# DSP.net
KiCad netlist of a schematic drawn in Altium Designer
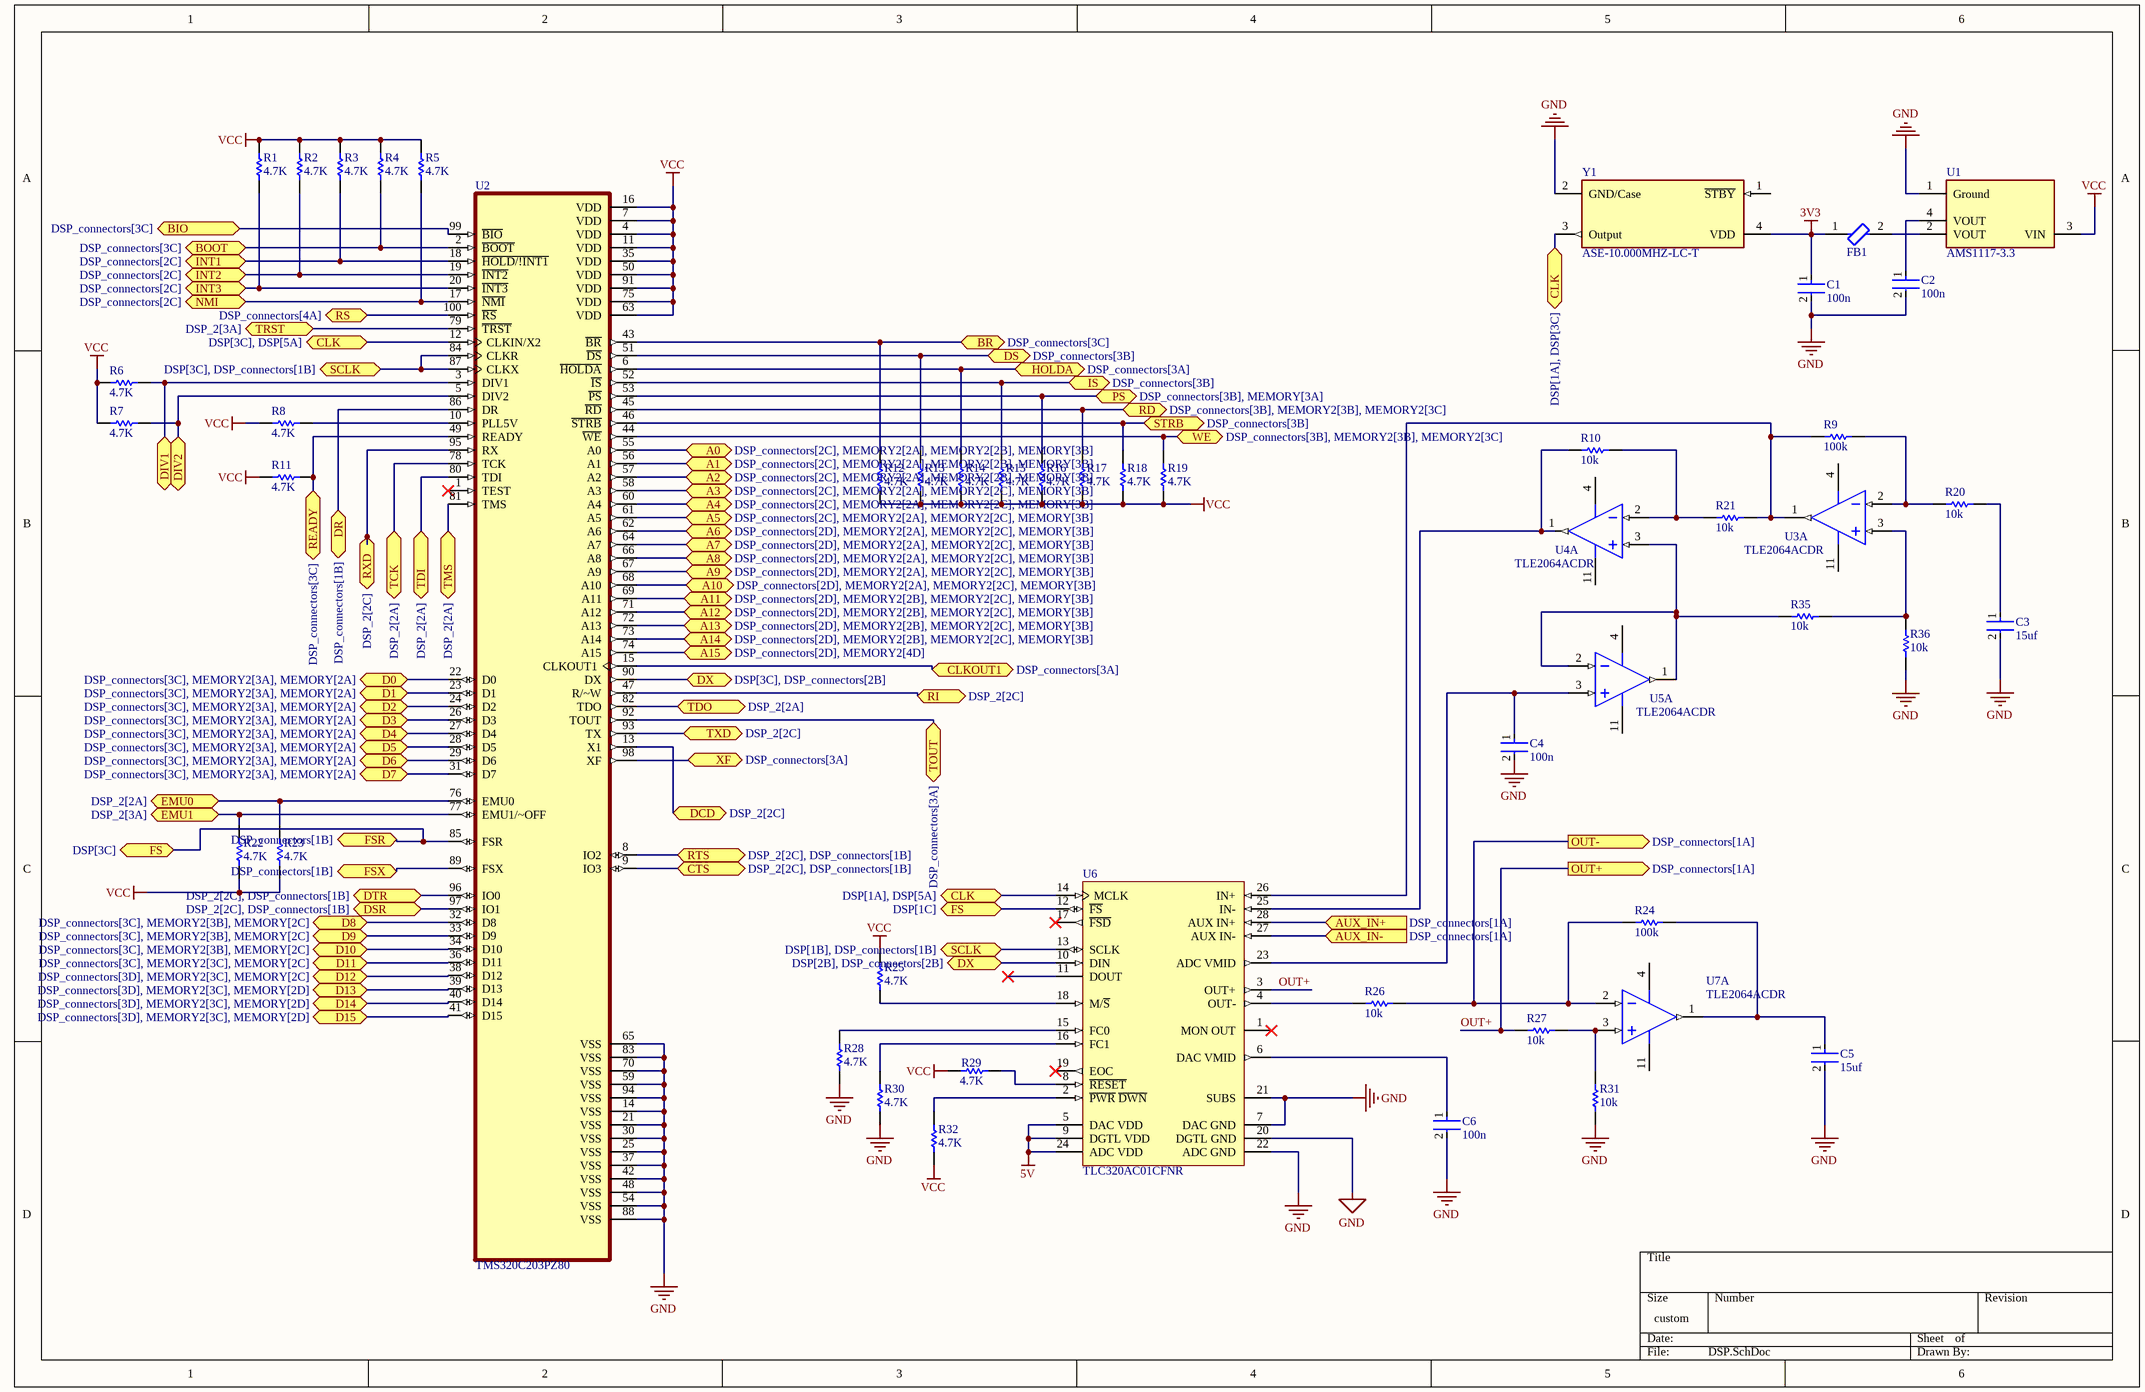
[diagram p0: DSP.SchDoc]

(export (version "E")
  (design (tool "Eeschema 10.0.6"))
  (components
    (comp (ref "C1")
      (value "100n")
      (footprint "FP-CL10-IPC_C")
      (description "Cap Ceramic 4.7uF 10V X5R ±10% Pad SMD 0603 +85°C T/R")
      (fields (field (name "TOLERANCE") "10%"))
      (libsource (lib "Altium Content Vault") (part "b4654b650e69147ec39a6b967a45e02"))
    )
    (comp (ref "C2")
      (value "100n")
      (footprint "FP-CL10-IPC_C")
      (description "Cap Ceramic 4.7uF 10V X5R ±10% Pad SMD 0603 +85°C T/R")
      (fields (field (name "TOLERANCE") "10%"))
      (libsource (lib "Altium Content Vault") (part "b4654b650e69147ec39a6b967a45e02"))
    )
    (comp (ref "C3")
      (value "15uf")
      (footprint "FP-CL10-IPC_C")
      (description "Cap Ceramic 4.7uF 10V X5R ±10% Pad SMD 0603 +85°C T/R")
      (fields (field (name "TOLERANCE") "10%"))
      (libsource (lib "Altium Content Vault") (part "b4654b650e69147ec39a6b967a45e02"))
    )
    (comp (ref "C4")
      (value "100n")
      (footprint "FP-CL10-IPC_C")
      (description "Cap Ceramic 4.7uF 10V X5R ±10% Pad SMD 0603 +85°C T/R")
      (fields (field (name "TOLERANCE") "10%"))
      (libsource (lib "Altium Content Vault") (part "b4654b650e69147ec39a6b967a45e02"))
    )
    (comp (ref "C5")
      (value "15uf")
      (footprint "FP-CL10-IPC_C")
      (description "Cap Ceramic 4.7uF 10V X5R ±10% Pad SMD 0603 +85°C T/R")
      (fields (field (name "TOLERANCE") "10%"))
      (libsource (lib "Altium Content Vault") (part "b4654b650e69147ec39a6b967a45e02"))
    )
    (comp (ref "C6")
      (value "100n")
      (footprint "FP-CL10-IPC_C")
      (description "Cap Ceramic 4.7uF 10V X5R ±10% Pad SMD 0603 +85°C T/R")
      (fields (field (name "TOLERANCE") "10%"))
      (libsource (lib "Altium Content Vault") (part "b4654b650e69147ec39a6b967a45e02"))
    )
    (comp (ref "FB1")
      (value "BLM18KG121TN1D")
      (footprint "FP-BLM18-0_15-t0_6-d1_2-IPC_A")
      (description "FERRITE BEAD 120 OHM 0603 1LN")
      (fields (field (name "TOLERANCE") "25%"))
      (libsource (lib "Altium Content Vault") (part "5f30dd21d616792df468990f7003faa"))
    )
    (comp (ref "R1")
      (value "4.7K")
      (footprint "RESC2013X60X35ML10T20")
      (fields (field (name "TOLERANCE") "5%") (field (name "MANUFACTURER") "Yageo"))
      (libsource (lib "Altium Content Vault") (part "RES-2"))
    )
    (comp (ref "R2")
      (value "4.7K")
      (footprint "RESC2013X60X35ML10T20")
      (fields (field (name "TOLERANCE") "5%") (field (name "MANUFACTURER") "Yageo"))
      (libsource (lib "Altium Content Vault") (part "RES-2"))
    )
    (comp (ref "R3")
      (value "4.7K")
      (footprint "RESC2013X60X35ML10T20")
      (fields (field (name "TOLERANCE") "5%") (field (name "MANUFACTURER") "Yageo"))
      (libsource (lib "Altium Content Vault") (part "RES-2"))
    )
    (comp (ref "R4")
      (value "4.7K")
      (footprint "RESC2013X60X35ML10T20")
      (fields (field (name "TOLERANCE") "5%") (field (name "MANUFACTURER") "Yageo"))
      (libsource (lib "Altium Content Vault") (part "RES-2"))
    )
    (comp (ref "R5")
      (value "4.7K")
      (footprint "RESC2013X60X35ML10T20")
      (fields (field (name "TOLERANCE") "5%") (field (name "MANUFACTURER") "Yageo"))
      (libsource (lib "Altium Content Vault") (part "RES-2"))
    )
    (comp (ref "R6")
      (value "4.7K")
      (footprint "RESC2013X60X35ML10T20")
      (fields (field (name "TOLERANCE") "5%") (field (name "MANUFACTURER") "Yageo"))
      (libsource (lib "Altium Content Vault") (part "RES-2"))
    )
    (comp (ref "R7")
      (value "4.7K")
      (footprint "RESC2013X60X35ML10T20")
      (fields (field (name "TOLERANCE") "5%") (field (name "MANUFACTURER") "Yageo"))
      (libsource (lib "Altium Content Vault") (part "RES-2"))
    )
    (comp (ref "R8")
      (value "4.7K")
      (footprint "RESC2013X60X35ML10T20")
      (fields (field (name "TOLERANCE") "5%") (field (name "MANUFACTURER") "Yageo"))
      (libsource (lib "Altium Content Vault") (part "RES-2"))
    )
    (comp (ref "R9")
      (value "100k")
      (footprint "RESC2013X60X35ML10T20")
      (fields (field (name "TOLERANCE") "5%") (field (name "MANUFACTURER") "Yageo"))
      (libsource (lib "Altium Content Vault") (part "RES-2"))
    )
    (comp (ref "R10")
      (value "10k")
      (footprint "RESC2013X60X35ML10T20")
      (fields (field (name "TOLERANCE") "5%") (field (name "MANUFACTURER") "Yageo"))
      (libsource (lib "Altium Content Vault") (part "RES-2"))
    )
    (comp (ref "R11")
      (value "4.7K")
      (footprint "RESC2013X60X35ML10T20")
      (fields (field (name "TOLERANCE") "5%") (field (name "MANUFACTURER") "Yageo"))
      (libsource (lib "Altium Content Vault") (part "RES-2"))
    )
    (comp (ref "R12")
      (value "4.7K")
      (footprint "RESC2013X60X35ML10T20")
      (fields (field (name "TOLERANCE") "5%") (field (name "MANUFACTURER") "Yageo"))
      (libsource (lib "Altium Content Vault") (part "RES-2"))
    )
    (comp (ref "R13")
      (value "4.7K")
      (footprint "RESC2013X60X35ML10T20")
      (fields (field (name "TOLERANCE") "5%") (field (name "MANUFACTURER") "Yageo"))
      (libsource (lib "Altium Content Vault") (part "RES-2"))
    )
    (comp (ref "R14")
      (value "4.7K")
      (footprint "RESC2013X60X35ML10T20")
      (fields (field (name "TOLERANCE") "5%") (field (name "MANUFACTURER") "Yageo"))
      (libsource (lib "Altium Content Vault") (part "RES-2"))
    )
    (comp (ref "R15")
      (value "4.7K")
      (footprint "RESC2013X60X35ML10T20")
      (fields (field (name "TOLERANCE") "5%") (field (name "MANUFACTURER") "Yageo"))
      (libsource (lib "Altium Content Vault") (part "RES-2"))
    )
    (comp (ref "R16")
      (value "4.7K")
      (footprint "RESC2013X60X35ML10T20")
      (fields (field (name "TOLERANCE") "5%") (field (name "MANUFACTURER") "Yageo"))
      (libsource (lib "Altium Content Vault") (part "RES-2"))
    )
    (comp (ref "R17")
      (value "4.7K")
      (footprint "RESC2013X60X35ML10T20")
      (fields (field (name "TOLERANCE") "5%") (field (name "MANUFACTURER") "Yageo"))
      (libsource (lib "Altium Content Vault") (part "RES-2"))
    )
    (comp (ref "R18")
      (value "4.7K")
      (footprint "RESC2013X60X35ML10T20")
      (fields (field (name "TOLERANCE") "5%") (field (name "MANUFACTURER") "Yageo"))
      (libsource (lib "Altium Content Vault") (part "RES-2"))
    )
    (comp (ref "R19")
      (value "4.7K")
      (footprint "RESC2013X60X35ML10T20")
      (fields (field (name "TOLERANCE") "5%") (field (name "MANUFACTURER") "Yageo"))
      (libsource (lib "Altium Content Vault") (part "RES-2"))
    )
    (comp (ref "R20")
      (value "10k")
      (footprint "RESC2013X60X35ML10T20")
      (fields (field (name "TOLERANCE") "5%") (field (name "MANUFACTURER") "Yageo"))
      (libsource (lib "Altium Content Vault") (part "RES-2"))
    )
    (comp (ref "R21")
      (value "10k")
      (footprint "RESC2013X60X35ML10T20")
      (fields (field (name "TOLERANCE") "5%") (field (name "MANUFACTURER") "Yageo"))
      (libsource (lib "Altium Content Vault") (part "RES-2"))
    )
    (comp (ref "R22")
      (value "4.7K")
      (footprint "RESC2013X60X35ML10T20")
      (fields (field (name "TOLERANCE") "5%") (field (name "MANUFACTURER") "Yageo"))
      (libsource (lib "Altium Content Vault") (part "RES-2"))
    )
    (comp (ref "R23")
      (value "4.7K")
      (footprint "RESC2013X60X35ML10T20")
      (fields (field (name "TOLERANCE") "5%") (field (name "MANUFACTURER") "Yageo"))
      (libsource (lib "Altium Content Vault") (part "RES-2"))
    )
    (comp (ref "R24")
      (value "100k")
      (footprint "RESC2013X60X35ML10T20")
      (fields (field (name "TOLERANCE") "5%") (field (name "MANUFACTURER") "Yageo"))
      (libsource (lib "Altium Content Vault") (part "RES-2"))
    )
    (comp (ref "R25")
      (value "4.7K")
      (footprint "RESC2013X60X35ML10T20")
      (fields (field (name "TOLERANCE") "5%") (field (name "MANUFACTURER") "Yageo"))
      (libsource (lib "Altium Content Vault") (part "RES-2"))
    )
    (comp (ref "R26")
      (value "10k")
      (footprint "RESC2013X60X35ML10T20")
      (fields (field (name "TOLERANCE") "5%") (field (name "MANUFACTURER") "Yageo"))
      (libsource (lib "Altium Content Vault") (part "RES-2"))
    )
    (comp (ref "R27")
      (value "10k")
      (footprint "RESC2013X60X35ML10T20")
      (fields (field (name "TOLERANCE") "5%") (field (name "MANUFACTURER") "Yageo"))
      (libsource (lib "Altium Content Vault") (part "RES-2"))
    )
    (comp (ref "R28")
      (value "4.7K")
      (footprint "RESC2013X60X35ML10T20")
      (fields (field (name "TOLERANCE") "5%") (field (name "MANUFACTURER") "Yageo"))
      (libsource (lib "Altium Content Vault") (part "RES-2"))
    )
    (comp (ref "R29")
      (value "4.7K")
      (footprint "RESC2013X60X35ML10T20")
      (fields (field (name "TOLERANCE") "5%") (field (name "MANUFACTURER") "Yageo"))
      (libsource (lib "Altium Content Vault") (part "RES-2"))
    )
    (comp (ref "R30")
      (value "4.7K")
      (footprint "RESC2013X60X35ML10T20")
      (fields (field (name "TOLERANCE") "5%") (field (name "MANUFACTURER") "Yageo"))
      (libsource (lib "Altium Content Vault") (part "RES-2"))
    )
    (comp (ref "R31")
      (value "10k")
      (footprint "RESC2013X60X35ML10T20")
      (fields (field (name "TOLERANCE") "5%") (field (name "MANUFACTURER") "Yageo"))
      (libsource (lib "Altium Content Vault") (part "RES-2"))
    )
    (comp (ref "R32")
      (value "4.7K")
      (footprint "RESC2013X60X35ML10T20")
      (fields (field (name "TOLERANCE") "5%") (field (name "MANUFACTURER") "Yageo"))
      (libsource (lib "Altium Content Vault") (part "RES-2"))
    )
    (comp (ref "R35")
      (value "10k")
      (footprint "RESC2013X60X35ML10T20")
      (fields (field (name "TOLERANCE") "5%") (field (name "MANUFACTURER") "Yageo"))
      (libsource (lib "Altium Content Vault") (part "RES-2"))
    )
    (comp (ref "R36")
      (value "10k")
      (footprint "RESC2013X60X35ML10T20")
      (fields (field (name "TOLERANCE") "5%") (field (name "MANUFACTURER") "Yageo"))
      (libsource (lib "Altium Content Vault") (part "RES-2"))
    )
    (comp (ref "U1")
      (value "AMS1117-3.3")
      (footprint "FP-AMS1117-IPC_C")
      (description "LDO Voltage Regulators 1A, 3.3V")
      (fields
        (field (name "OCTOPART") "https://octopart.com/ams1117-3.3-advanced+monolithic+systems-25899300")
        (field (name "MANUFACTURER") "Advanced Monolithic Systems")
      )
      (libsource (lib "Altium Content Vault") (part "8bdbb5f8e77002000e30dd2845d0354"))
    )
    (comp (ref "U2")
      (value "TMS320C203PZ80")
      (footprint "QFP50P1600X1600X160-100N")
      (libsource (lib "TMS320C203PZ80") (part "TMS320C203PZ80"))
    )
    (comp (ref "U3")
      (value "TLE2064ACDR")
      (footprint "D0014A_M")
      (fields (field (name "MANUFACTURER") "Texas Instruments"))
      (libsource (lib "Altium Content Vault") (part "TI-TLE2XXXXX-14"))
    )
    (comp (ref "U4")
      (value "TLE2064ACDR")
      (footprint "D0014A_M")
      (fields (field (name "MANUFACTURER") "Texas Instruments"))
      (libsource (lib "Altium Content Vault") (part "TI-TLE2XXXXX-14"))
    )
    (comp (ref "U5")
      (value "TLE2064ACDR")
      (footprint "D0014A_M")
      (fields (field (name "MANUFACTURER") "Texas Instruments"))
      (libsource (lib "Altium Content Vault") (part "TI-TLE2XXXXX-14"))
    )
    (comp (ref "U6")
      (value "TLC320AC01CFNR")
      (footprint "FN0028A_L")
      (fields (field (name "MANUFACTURER") "Texas Instruments"))
      (libsource (lib "Altium Content Vault") (part "TI-TLC320AC01FN28"))
    )
    (comp (ref "U7")
      (value "TLE2064ACDR")
      (footprint "D0014A_M")
      (fields (field (name "MANUFACTURER") "Texas Instruments"))
      (libsource (lib "Altium Content Vault") (part "TI-TLE2XXXXX-14"))
    )
    (comp (ref "Y1")
      (value "ASE-10.000MHZ-LC-T")
      (footprint "FP-ASE-MFG")
      (description "XTAL Oscillator 10MHz ±50ppm CMOS 3.3V 4-SMD 3.2mm x 2.5mm")
      (libsource (lib "Altium Content Vault") (part "61a724e6190563596ac712fef61ad37"))
    )
  )
  (nets
    (net (code "1") (name "/A0") (class "Default")
      (node (ref "U2") (pin "55") (pinfunction "A0_55") (pintype "output"))
    )
    (net (code "2") (name "/A1") (class "Default")
      (node (ref "U2") (pin "56") (pinfunction "A1_56") (pintype "output"))
    )
    (net (code "3") (name "/A2") (class "Default")
      (node (ref "U2") (pin "57") (pinfunction "A2_57") (pintype "output"))
    )
    (net (code "4") (name "/A3") (class "Default")
      (node (ref "U2") (pin "58") (pinfunction "A3_58") (pintype "output"))
    )
    (net (code "5") (name "/A4") (class "Default")
      (node (ref "U2") (pin "60") (pinfunction "A4_60") (pintype "output"))
    )
    (net (code "6") (name "/A5") (class "Default")
      (node (ref "U2") (pin "61") (pinfunction "A5_61") (pintype "output"))
    )
    (net (code "7") (name "/A6") (class "Default")
      (node (ref "U2") (pin "62") (pinfunction "A6_62") (pintype "output"))
    )
    (net (code "8") (name "/A7") (class "Default")
      (node (ref "U2") (pin "64") (pinfunction "A7_64") (pintype "output"))
    )
    (net (code "9") (name "/A8") (class "Default")
      (node (ref "U2") (pin "66") (pinfunction "A8_66") (pintype "output"))
    )
    (net (code "10") (name "/A9") (class "Default")
      (node (ref "U2") (pin "67") (pinfunction "A9_67") (pintype "output"))
    )
    (net (code "11") (name "/A10") (class "Default")
      (node (ref "U2") (pin "68") (pinfunction "A10_68") (pintype "output"))
    )
    (net (code "12") (name "/A11") (class "Default")
      (node (ref "U2") (pin "69") (pinfunction "A11_69") (pintype "output"))
    )
    (net (code "13") (name "/A12") (class "Default")
      (node (ref "U2") (pin "71") (pinfunction "A12_71") (pintype "output"))
    )
    (net (code "14") (name "/A13") (class "Default")
      (node (ref "U2") (pin "72") (pinfunction "A13_72") (pintype "output"))
    )
    (net (code "15") (name "/A14") (class "Default")
      (node (ref "U2") (pin "73") (pinfunction "A14_73") (pintype "output"))
    )
    (net (code "16") (name "/A15") (class "Default")
      (node (ref "U2") (pin "74") (pinfunction "A15_74") (pintype "output"))
    )
    (net (code "17") (name "/AUX_IN+") (class "Default")
      (node (ref "U6") (pin "28") (pinfunction "AUX_IN+_28") (pintype "input"))
    )
    (net (code "18") (name "/AUX_IN-") (class "Default")
      (node (ref "U6") (pin "27") (pinfunction "AUX_IN-_27") (pintype "input"))
    )
    (net (code "19") (name "/BIO") (class "Default")
      (node (ref "U2") (pin "99") (pinfunction "~{BIO}_99") (pintype "input"))
    )
    (net (code "20") (name "/BOOT") (class "Default")
      (node (ref "R4") (pin "1") (pinfunction "1_1") (pintype "passive"))
      (node (ref "U2") (pin "2") (pinfunction "~{BOOT}_2") (pintype "input"))
    )
    (net (code "21") (name "/BR") (class "Default")
      (node (ref "R12") (pin "1") (pinfunction "1_1") (pintype "passive"))
      (node (ref "U2") (pin "43") (pinfunction "~{BR}_43") (pintype "output"))
    )
    (net (code "22") (name "/CLK") (class "Default")
      (node (ref "U2") (pin "12") (pinfunction "CLKIN/X2_12") (pintype "input"))
      (node (ref "U6") (pin "14") (pinfunction "MCLK_14") (pintype "input"))
      (node (ref "Y1") (pin "3") (pinfunction "Output_3") (pintype "output"))
    )
    (net (code "23") (name "/CLKOUT1") (class "Default")
      (node (ref "U2") (pin "15") (pinfunction "CLKOUT1_15") (pintype "output"))
    )
    (net (code "24") (name "/CTS") (class "Default")
      (node (ref "U2") (pin "9") (pinfunction "IO3_9") (pintype "bidirectional"))
    )
    (net (code "25") (name "/D0") (class "Default")
      (node (ref "U2") (pin "22") (pinfunction "D0_22") (pintype "bidirectional"))
    )
    (net (code "26") (name "/D1") (class "Default")
      (node (ref "U2") (pin "23") (pinfunction "D1_23") (pintype "bidirectional"))
    )
    (net (code "27") (name "/D2") (class "Default")
      (node (ref "U2") (pin "24") (pinfunction "D2_24") (pintype "bidirectional"))
    )
    (net (code "28") (name "/D3") (class "Default")
      (node (ref "U2") (pin "26") (pinfunction "D3_26") (pintype "bidirectional"))
    )
    (net (code "29") (name "/D4") (class "Default")
      (node (ref "U2") (pin "27") (pinfunction "D4_27") (pintype "bidirectional"))
    )
    (net (code "30") (name "/D5") (class "Default")
      (node (ref "U2") (pin "28") (pinfunction "D5_28") (pintype "bidirectional"))
    )
    (net (code "31") (name "/D6") (class "Default")
      (node (ref "U2") (pin "29") (pinfunction "D6_29") (pintype "bidirectional"))
    )
    (net (code "32") (name "/D7") (class "Default")
      (node (ref "U2") (pin "31") (pinfunction "D7_31") (pintype "bidirectional"))
    )
    (net (code "33") (name "/D8") (class "Default")
      (node (ref "U2") (pin "32") (pinfunction "D8_32") (pintype "bidirectional"))
    )
    (net (code "34") (name "/D9") (class "Default")
      (node (ref "U2") (pin "33") (pinfunction "D9_33") (pintype "bidirectional"))
    )
    (net (code "35") (name "/D10") (class "Default")
      (node (ref "U2") (pin "34") (pinfunction "D10_34") (pintype "bidirectional"))
    )
    (net (code "36") (name "/D11") (class "Default")
      (node (ref "U2") (pin "36") (pinfunction "D11_36") (pintype "bidirectional"))
    )
    (net (code "37") (name "/D12") (class "Default")
      (node (ref "U2") (pin "38") (pinfunction "D12_38") (pintype "bidirectional"))
    )
    (net (code "38") (name "/D13") (class "Default")
      (node (ref "U2") (pin "39") (pinfunction "D13_39") (pintype "bidirectional"))
    )
    (net (code "39") (name "/D14") (class "Default")
      (node (ref "U2") (pin "40") (pinfunction "D14_40") (pintype "bidirectional"))
    )
    (net (code "40") (name "/D15") (class "Default")
      (node (ref "U2") (pin "41") (pinfunction "D15_41") (pintype "bidirectional"))
    )
    (net (code "41") (name "/DCD") (class "Default")
      (node (ref "U2") (pin "13") (pinfunction "X1_13") (pintype "output"))
    )
    (net (code "42") (name "/DIV1") (class "Default")
      (node (ref "R6") (pin "1") (pinfunction "1_1") (pintype "passive"))
      (node (ref "U2") (pin "3") (pinfunction "DIV1_3") (pintype "input"))
    )
    (net (code "43") (name "/DIV2") (class "Default")
      (node (ref "R7") (pin "1") (pinfunction "1_1") (pintype "passive"))
      (node (ref "U2") (pin "5") (pinfunction "DIV2_5") (pintype "input"))
    )
    (net (code "44") (name "/DR") (class "Default")
      (node (ref "U2") (pin "86") (pinfunction "DR_86") (pintype "input"))
    )
    (net (code "45") (name "/DS") (class "Default")
      (node (ref "R13") (pin "1") (pinfunction "1_1") (pintype "passive"))
      (node (ref "U2") (pin "51") (pinfunction "~{DS}_51") (pintype "output"))
    )
    (net (code "46") (name "/DSR") (class "Default")
      (node (ref "U2") (pin "97") (pinfunction "IO1_97") (pintype "bidirectional"))
    )
    (net (code "47") (name "/DTR") (class "Default")
      (node (ref "U2") (pin "96") (pinfunction "IO0_96") (pintype "bidirectional"))
    )
    (net (code "48") (name "/DX") (class "Default")
      (node (ref "U2") (pin "90") (pinfunction "DX_90") (pintype "output"))
      (node (ref "U6") (pin "10") (pinfunction "DIN_10") (pintype "input"))
    )
    (net (code "49") (name "/EMU0") (class "Default")
      (node (ref "R23") (pin "2") (pinfunction "2_2") (pintype "passive"))
      (node (ref "U2") (pin "76") (pinfunction "EMU0_76") (pintype "bidirectional"))
    )
    (net (code "50") (name "/EMU1") (class "Default")
      (node (ref "R22") (pin "2") (pinfunction "2_2") (pintype "passive"))
      (node (ref "U2") (pin "77") (pinfunction "EMU1/~OFF_77") (pintype "bidirectional"))
    )
    (net (code "51") (name "/FS") (class "Default")
      (node (ref "U2") (pin "85") (pinfunction "FSR_85") (pintype "bidirectional"))
      (node (ref "U6") (pin "12") (pinfunction "~{FS}_12") (pintype "bidirectional"))
    )
    (net (code "52") (name "/FSX") (class "Default")
      (node (ref "U2") (pin "89") (pinfunction "FSX_89") (pintype "bidirectional"))
    )
    (net (code "53") (name "/HOLDA") (class "Default")
      (node (ref "R14") (pin "1") (pinfunction "1_1") (pintype "passive"))
      (node (ref "U2") (pin "6") (pinfunction "~{HOLDA}_6") (pintype "output"))
    )
    (net (code "54") (name "/INT1") (class "Default")
      (node (ref "R3") (pin "1") (pinfunction "1_1") (pintype "passive"))
      (node (ref "U2") (pin "18") (pinfunction "~{HOLD/!INT1}_18") (pintype "input"))
    )
    (net (code "55") (name "/INT2") (class "Default")
      (node (ref "R2") (pin "1") (pinfunction "1_1") (pintype "passive"))
      (node (ref "U2") (pin "19") (pinfunction "~{INT2}_19") (pintype "input"))
    )
    (net (code "56") (name "/INT3") (class "Default")
      (node (ref "R1") (pin "1") (pinfunction "1_1") (pintype "passive"))
      (node (ref "U2") (pin "20") (pinfunction "~{INT3}_20") (pintype "input"))
    )
    (net (code "57") (name "/IS") (class "Default")
      (node (ref "R15") (pin "1") (pinfunction "1_1") (pintype "passive"))
      (node (ref "U2") (pin "52") (pinfunction "~{IS}_52") (pintype "output"))
    )
    (net (code "58") (name "/NMI") (class "Default")
      (node (ref "R5") (pin "1") (pinfunction "1_1") (pintype "passive"))
      (node (ref "U2") (pin "17") (pinfunction "~{NMI}_17") (pintype "input"))
    )
    (net (code "59") (name "/OUT+") (class "Default")
      (node (ref "R27") (pin "2") (pinfunction "2_2") (pintype "passive"))
      (node (ref "U6") (pin "3") (pinfunction "OUT+_3") (pintype "output"))
    )
    (net (code "60") (name "/OUT-") (class "Default")
      (node (ref "R24") (pin "2") (pinfunction "2_2") (pintype "passive"))
      (node (ref "R26") (pin "1") (pinfunction "1_1") (pintype "passive"))
      (node (ref "U7") (pin "2") (pinfunction "IN1-_2") (pintype "input"))
    )
    (net (code "61") (name "/PS") (class "Default")
      (node (ref "R16") (pin "1") (pinfunction "1_1") (pintype "passive"))
      (node (ref "U2") (pin "53") (pinfunction "~{PS}_53") (pintype "output"))
    )
    (net (code "62") (name "/RD") (class "Default")
      (node (ref "R17") (pin "1") (pinfunction "1_1") (pintype "passive"))
      (node (ref "U2") (pin "45") (pinfunction "~{RD}_45") (pintype "output"))
    )
    (net (code "63") (name "/READY") (class "Default")
      (node (ref "R11") (pin "2") (pinfunction "2_2") (pintype "passive"))
      (node (ref "U2") (pin "49") (pinfunction "READY_49") (pintype "input"))
    )
    (net (code "64") (name "/RI") (class "Default")
      (node (ref "U2") (pin "47") (pinfunction "R/~W_47") (pintype "output"))
    )
    (net (code "65") (name "/RS") (class "Default")
      (node (ref "U2") (pin "100") (pinfunction "~{RS}_100") (pintype "input"))
    )
    (net (code "66") (name "/RTS") (class "Default")
      (node (ref "U2") (pin "8") (pinfunction "IO2_8") (pintype "bidirectional"))
    )
    (net (code "67") (name "/RXD") (class "Default")
      (node (ref "U2") (pin "95") (pinfunction "RX_95") (pintype "input"))
    )
    (net (code "68") (name "/SCLK") (class "Default")
      (node (ref "U2") (pin "84") (pinfunction "CLKR_84") (pintype "input"))
      (node (ref "U2") (pin "87") (pinfunction "CLKX_87") (pintype "input"))
      (node (ref "U6") (pin "13") (pinfunction "SCLK_13") (pintype "bidirectional"))
    )
    (net (code "69") (name "/STRB") (class "Default")
      (node (ref "R18") (pin "1") (pinfunction "1_1") (pintype "passive"))
      (node (ref "U2") (pin "46") (pinfunction "~{STRB}_46") (pintype "output"))
    )
    (net (code "70") (name "/TCK") (class "Default")
      (node (ref "U2") (pin "78") (pinfunction "TCK_78") (pintype "input"))
    )
    (net (code "71") (name "/TDI") (class "Default")
      (node (ref "U2") (pin "80") (pinfunction "TDI_80") (pintype "input"))
    )
    (net (code "72") (name "/TDO") (class "Default")
      (node (ref "U2") (pin "82") (pinfunction "TDO_82") (pintype "output"))
    )
    (net (code "73") (name "/TMS") (class "Default")
      (node (ref "U2") (pin "81") (pinfunction "TMS_81") (pintype "input"))
    )
    (net (code "74") (name "/TOUT") (class "Default")
      (node (ref "U2") (pin "92") (pinfunction "TOUT_92") (pintype "output"))
    )
    (net (code "75") (name "/TRST") (class "Default")
      (node (ref "U2") (pin "79") (pinfunction "~{TRST}_79") (pintype "input"))
    )
    (net (code "76") (name "/TXD") (class "Default")
      (node (ref "U2") (pin "93") (pinfunction "TX_93") (pintype "output"))
    )
    (net (code "77") (name "/WE") (class "Default")
      (node (ref "R19") (pin "1") (pinfunction "1_1") (pintype "passive"))
      (node (ref "U2") (pin "44") (pinfunction "~{WE}_44") (pintype "output"))
    )
    (net (code "78") (name "/XF") (class "Default")
      (node (ref "U2") (pin "98") (pinfunction "XF_98") (pintype "output"))
    )
    (net (code "79") (name "3V3") (class "Default")
      (node (ref "C1") (pin "1") (pinfunction "1_1") (pintype "passive"))
      (node (ref "FB1") (pin "1") (pinfunction "1_1") (pintype "passive"))
      (node (ref "Y1") (pin "4") (pinfunction "VDD_4") (pintype "power_in"))
    )
    (net (code "80") (name "5V") (class "Default")
      (node (ref "U6") (pin "24") (pinfunction "ADC_VDD_24") (pintype "power_in"))
      (node (ref "U6") (pin "5") (pinfunction "DAC_VDD_5") (pintype "power_in"))
      (node (ref "U6") (pin "9") (pinfunction "DGTL_VDD_9") (pintype "power_in"))
    )
    (net (code "81") (name "GND") (class "Default")
      (node (ref "C1") (pin "2") (pinfunction "2_2") (pintype "passive"))
      (node (ref "C2") (pin "2") (pinfunction "2_2") (pintype "passive"))
      (node (ref "C3") (pin "2") (pinfunction "2_2") (pintype "passive"))
      (node (ref "C4") (pin "2") (pinfunction "2_2") (pintype "passive"))
      (node (ref "C5") (pin "2") (pinfunction "2_2") (pintype "passive"))
      (node (ref "C6") (pin "2") (pinfunction "2_2") (pintype "passive"))
      (node (ref "R28") (pin "2") (pinfunction "2_2") (pintype "passive"))
      (node (ref "R30") (pin "1") (pinfunction "1_1") (pintype "passive"))
      (node (ref "R31") (pin "1") (pinfunction "1_1") (pintype "passive"))
      (node (ref "R36") (pin "2") (pinfunction "2_2") (pintype "passive"))
      (node (ref "U1") (pin "1") (pinfunction "Ground_1") (pintype "power_in"))
      (node (ref "U2") (pin "14") (pinfunction "VSS_14") (pintype "power_in"))
      (node (ref "U2") (pin "21") (pinfunction "VSS_21") (pintype "power_in"))
      (node (ref "U2") (pin "25") (pinfunction "VSS_25") (pintype "power_in"))
      (node (ref "U2") (pin "30") (pinfunction "VSS_30") (pintype "power_in"))
      (node (ref "U2") (pin "37") (pinfunction "VSS_37") (pintype "power_in"))
      (node (ref "U2") (pin "42") (pinfunction "VSS_42") (pintype "power_in"))
      (node (ref "U2") (pin "48") (pinfunction "VSS_48") (pintype "power_in"))
      (node (ref "U2") (pin "54") (pinfunction "VSS_54") (pintype "power_in"))
      (node (ref "U2") (pin "59") (pinfunction "VSS_59") (pintype "power_in"))
      (node (ref "U2") (pin "65") (pinfunction "VSS_65") (pintype "power_in"))
      (node (ref "U2") (pin "70") (pinfunction "VSS_70") (pintype "power_in"))
      (node (ref "U2") (pin "83") (pinfunction "VSS_83") (pintype "power_in"))
      (node (ref "U2") (pin "88") (pinfunction "VSS_88") (pintype "power_in"))
      (node (ref "U2") (pin "94") (pinfunction "VSS_94") (pintype "power_in"))
      (node (ref "U6") (pin "20") (pinfunction "DGTL_GND_20") (pintype "power_in"))
      (node (ref "U6") (pin "21") (pinfunction "SUBS_21") (pintype "power_in"))
      (node (ref "U6") (pin "22") (pinfunction "ADC_GND_22") (pintype "power_in"))
      (node (ref "U6") (pin "7") (pinfunction "DAC_GND_7") (pintype "power_in"))
      (node (ref "Y1") (pin "2") (pinfunction "GND/Case_2") (pintype "power_in"))
    )
    (net (code "82") (name "Net-(C2-Pad1)") (class "Default")
      (node (ref "C2") (pin "1") (pinfunction "1_1") (pintype "passive"))
      (node (ref "U1") (pin "4") (pinfunction "VOUT_4") (pintype "passive"))
    )
    (net (code "83") (name "Net-(C3-Pad1)") (class "Default")
      (node (ref "C3") (pin "1") (pinfunction "1_1") (pintype "passive"))
      (node (ref "R20") (pin "2") (pinfunction "2_2") (pintype "passive"))
    )
    (net (code "84") (name "Net-(FB1-Pad2)") (class "Default")
      (node (ref "FB1") (pin "2") (pinfunction "2_2") (pintype "passive"))
      (node (ref "U1") (pin "2") (pinfunction "VOUT_2") (pintype "passive"))
    )
    (net (code "85") (name "Net-(U2-PLL5V)") (class "Default")
      (node (ref "R8") (pin "2") (pinfunction "2_2") (pintype "passive"))
      (node (ref "U2") (pin "10") (pinfunction "PLL5V_10") (pintype "input"))
    )
    (net (code "86") (name "Net-(U3A-IN1+)") (class "Default")
      (node (ref "R35") (pin "1") (pinfunction "1_1") (pintype "passive"))
      (node (ref "R36") (pin "1") (pinfunction "1_1") (pintype "passive"))
      (node (ref "U3") (pin "3") (pinfunction "IN1+_3") (pintype "input"))
    )
    (net (code "87") (name "Net-(U3A-IN1-)") (class "Default")
      (node (ref "R20") (pin "1") (pinfunction "1_1") (pintype "passive"))
      (node (ref "R9") (pin "1") (pinfunction "1_1") (pintype "passive"))
      (node (ref "U3") (pin "2") (pinfunction "IN1-_2") (pintype "input"))
    )
    (net (code "88") (name "Net-(U3A-OUT1)") (class "Default")
      (node (ref "R21") (pin "1") (pinfunction "1_1") (pintype "passive"))
      (node (ref "R9") (pin "2") (pinfunction "2_2") (pintype "passive"))
      (node (ref "U3") (pin "1") (pinfunction "OUT1_1") (pintype "output"))
      (node (ref "U6") (pin "26") (pinfunction "IN+_26") (pintype "input"))
    )
    (net (code "89") (name "Net-(U4A-IN1+)") (class "Default")
      (node (ref "R35") (pin "2") (pinfunction "2_2") (pintype "passive"))
      (node (ref "U4") (pin "3") (pinfunction "IN1+_3") (pintype "input"))
      (node (ref "U5") (pin "1") (pinfunction "OUT1_1") (pintype "output"))
      (node (ref "U5") (pin "2") (pinfunction "IN1-_2") (pintype "input"))
    )
    (net (code "90") (name "Net-(U4A-IN1-)") (class "Default")
      (node (ref "R10") (pin "1") (pinfunction "1_1") (pintype "passive"))
      (node (ref "R21") (pin "2") (pinfunction "2_2") (pintype "passive"))
      (node (ref "U4") (pin "2") (pinfunction "IN1-_2") (pintype "input"))
    )
    (net (code "91") (name "Net-(U4A-OUT1)") (class "Default")
      (node (ref "R10") (pin "2") (pinfunction "2_2") (pintype "passive"))
      (node (ref "U4") (pin "1") (pinfunction "OUT1_1") (pintype "output"))
      (node (ref "U6") (pin "25") (pinfunction "IN-_25") (pintype "input"))
    )
    (net (code "92") (name "Net-(U5A-IN1+)") (class "Default")
      (node (ref "C4") (pin "1") (pinfunction "1_1") (pintype "passive"))
      (node (ref "U5") (pin "3") (pinfunction "IN1+_3") (pintype "input"))
      (node (ref "U6") (pin "23") (pinfunction "ADC_VMID_23") (pintype "output"))
    )
    (net (code "93") (name "Net-(U6-DAC_VMID)") (class "Default")
      (node (ref "C6") (pin "1") (pinfunction "1_1") (pintype "passive"))
      (node (ref "U6") (pin "6") (pinfunction "DAC_VMID_6") (pintype "output"))
    )
    (net (code "94") (name "Net-(U6-FC0)") (class "Default")
      (node (ref "R28") (pin "1") (pinfunction "1_1") (pintype "passive"))
      (node (ref "U6") (pin "15") (pinfunction "FC0_15") (pintype "input"))
    )
    (net (code "95") (name "Net-(U6-FC1)") (class "Default")
      (node (ref "R30") (pin "2") (pinfunction "2_2") (pintype "passive"))
      (node (ref "U6") (pin "16") (pinfunction "FC1_16") (pintype "input"))
    )
    (net (code "96") (name "Net-(U6-M{slash}~{S})") (class "Default")
      (node (ref "R25") (pin "1") (pinfunction "1_1") (pintype "passive"))
      (node (ref "U6") (pin "18") (pinfunction "M/~{S}_18") (pintype "input"))
    )
    (net (code "97") (name "Net-(U6-OUT-)") (class "Default")
      (node (ref "R26") (pin "2") (pinfunction "2_2") (pintype "passive"))
      (node (ref "U6") (pin "4") (pinfunction "OUT-_4") (pintype "output"))
    )
    (net (code "98") (name "Net-(U6-~{PWR}_~{DWN})") (class "Default")
      (node (ref "R32") (pin "2") (pinfunction "2_2") (pintype "passive"))
      (node (ref "U6") (pin "2") (pinfunction "~{PWR}_~{DWN}_2") (pintype "input"))
    )
    (net (code "99") (name "Net-(U6-~{RESET})") (class "Default")
      (node (ref "R29") (pin "1") (pinfunction "1_1") (pintype "passive"))
      (node (ref "U6") (pin "8") (pinfunction "~{RESET}_8") (pintype "input"))
    )
    (net (code "100") (name "Net-(U7A-IN1+)") (class "Default")
      (node (ref "R27") (pin "1") (pinfunction "1_1") (pintype "passive"))
      (node (ref "R31") (pin "2") (pinfunction "2_2") (pintype "passive"))
      (node (ref "U7") (pin "3") (pinfunction "IN1+_3") (pintype "input"))
    )
    (net (code "101") (name "Net-(U7A-OUT1)") (class "Default")
      (node (ref "C5") (pin "1") (pinfunction "1_1") (pintype "passive"))
      (node (ref "R24") (pin "1") (pinfunction "1_1") (pintype "passive"))
      (node (ref "U7") (pin "1") (pinfunction "OUT1_1") (pintype "output"))
    )
    (net (code "102") (name "VCC") (class "Default")
      (node (ref "R1") (pin "2") (pinfunction "2_2") (pintype "passive"))
      (node (ref "R11") (pin "1") (pinfunction "1_1") (pintype "passive"))
      (node (ref "R12") (pin "2") (pinfunction "2_2") (pintype "passive"))
      (node (ref "R13") (pin "2") (pinfunction "2_2") (pintype "passive"))
      (node (ref "R14") (pin "2") (pinfunction "2_2") (pintype "passive"))
      (node (ref "R15") (pin "2") (pinfunction "2_2") (pintype "passive"))
      (node (ref "R16") (pin "2") (pinfunction "2_2") (pintype "passive"))
      (node (ref "R17") (pin "2") (pinfunction "2_2") (pintype "passive"))
      (node (ref "R18") (pin "2") (pinfunction "2_2") (pintype "passive"))
      (node (ref "R19") (pin "2") (pinfunction "2_2") (pintype "passive"))
      (node (ref "R2") (pin "2") (pinfunction "2_2") (pintype "passive"))
      (node (ref "R22") (pin "1") (pinfunction "1_1") (pintype "passive"))
      (node (ref "R23") (pin "1") (pinfunction "1_1") (pintype "passive"))
      (node (ref "R25") (pin "2") (pinfunction "2_2") (pintype "passive"))
      (node (ref "R29") (pin "2") (pinfunction "2_2") (pintype "passive"))
      (node (ref "R3") (pin "2") (pinfunction "2_2") (pintype "passive"))
      (node (ref "R32") (pin "1") (pinfunction "1_1") (pintype "passive"))
      (node (ref "R4") (pin "2") (pinfunction "2_2") (pintype "passive"))
      (node (ref "R5") (pin "2") (pinfunction "2_2") (pintype "passive"))
      (node (ref "R6") (pin "2") (pinfunction "2_2") (pintype "passive"))
      (node (ref "R7") (pin "2") (pinfunction "2_2") (pintype "passive"))
      (node (ref "R8") (pin "1") (pinfunction "1_1") (pintype "passive"))
      (node (ref "U1") (pin "3") (pinfunction "VIN_3") (pintype "power_in"))
      (node (ref "U2") (pin "11") (pinfunction "VDD_11") (pintype "power_in"))
      (node (ref "U2") (pin "16") (pinfunction "VDD_16") (pintype "power_in"))
      (node (ref "U2") (pin "35") (pinfunction "VDD_35") (pintype "power_in"))
      (node (ref "U2") (pin "4") (pinfunction "VDD_4") (pintype "power_in"))
      (node (ref "U2") (pin "50") (pinfunction "VDD_50") (pintype "power_in"))
      (node (ref "U2") (pin "63") (pinfunction "VDD_63") (pintype "power_in"))
      (node (ref "U2") (pin "7") (pinfunction "VDD_7") (pintype "power_in"))
      (node (ref "U2") (pin "75") (pinfunction "VDD_75") (pintype "power_in"))
      (node (ref "U2") (pin "91") (pinfunction "VDD_91") (pintype "power_in"))
    )
    (net (code "103") (name "unconnected-(U2-TEST-Pad1)") (class "Default")
      (node (ref "U2") (pin "1") (pinfunction "TEST_1") (pintype "input+no_connect"))
    )
    (net (code "104") (name "unconnected-(U3A-VCC+-Pad4)") (class "Default")
      (node (ref "U3") (pin "4") (pinfunction "VCC+_4") (pintype "power_in"))
    )
    (net (code "105") (name "unconnected-(U3A-VCC--Pad11)") (class "Default")
      (node (ref "U3") (pin "11") (pinfunction "VCC-_11") (pintype "power_in"))
    )
    (net (code "106") (name "unconnected-(U4A-VCC+-Pad4)") (class "Default")
      (node (ref "U4") (pin "4") (pinfunction "VCC+_4") (pintype "power_in"))
    )
    (net (code "107") (name "unconnected-(U4A-VCC--Pad11)") (class "Default")
      (node (ref "U4") (pin "11") (pinfunction "VCC-_11") (pintype "power_in"))
    )
    (net (code "108") (name "unconnected-(U5A-VCC+-Pad4)") (class "Default")
      (node (ref "U5") (pin "4") (pinfunction "VCC+_4") (pintype "power_in"))
    )
    (net (code "109") (name "unconnected-(U5A-VCC--Pad11)") (class "Default")
      (node (ref "U5") (pin "11") (pinfunction "VCC-_11") (pintype "power_in"))
    )
    (net (code "110") (name "unconnected-(U6-DOUT-Pad11)") (class "Default")
      (node (ref "U6") (pin "11") (pinfunction "DOUT_11") (pintype "tri_state+no_connect"))
    )
    (net (code "111") (name "unconnected-(U6-EOC-Pad19)") (class "Default")
      (node (ref "U6") (pin "19") (pinfunction "EOC_19") (pintype "output+no_connect"))
    )
    (net (code "112") (name "unconnected-(U6-MON_OUT-Pad1)") (class "Default")
      (node (ref "U6") (pin "1") (pinfunction "MON_OUT_1") (pintype "tri_state+no_connect"))
    )
    (net (code "113") (name "unconnected-(U6-~{FSD}-Pad17)") (class "Default")
      (node (ref "U6") (pin "17") (pinfunction "~{FSD}_17") (pintype "output+no_connect"))
    )
    (net (code "114") (name "unconnected-(U7A-VCC+-Pad4)") (class "Default")
      (node (ref "U7") (pin "4") (pinfunction "VCC+_4") (pintype "power_in"))
    )
    (net (code "115") (name "unconnected-(U7A-VCC--Pad11)") (class "Default")
      (node (ref "U7") (pin "11") (pinfunction "VCC-_11") (pintype "power_in"))
    )
    (net (code "116") (name "unconnected-(Y1-~{STBY}-Pad1)") (class "Default")
      (node (ref "Y1") (pin "1") (pinfunction "~{STBY}_1") (pintype "input"))
    )
  )
)
